# working.net
KiCad netlist of a schematic drawn in EAGLE
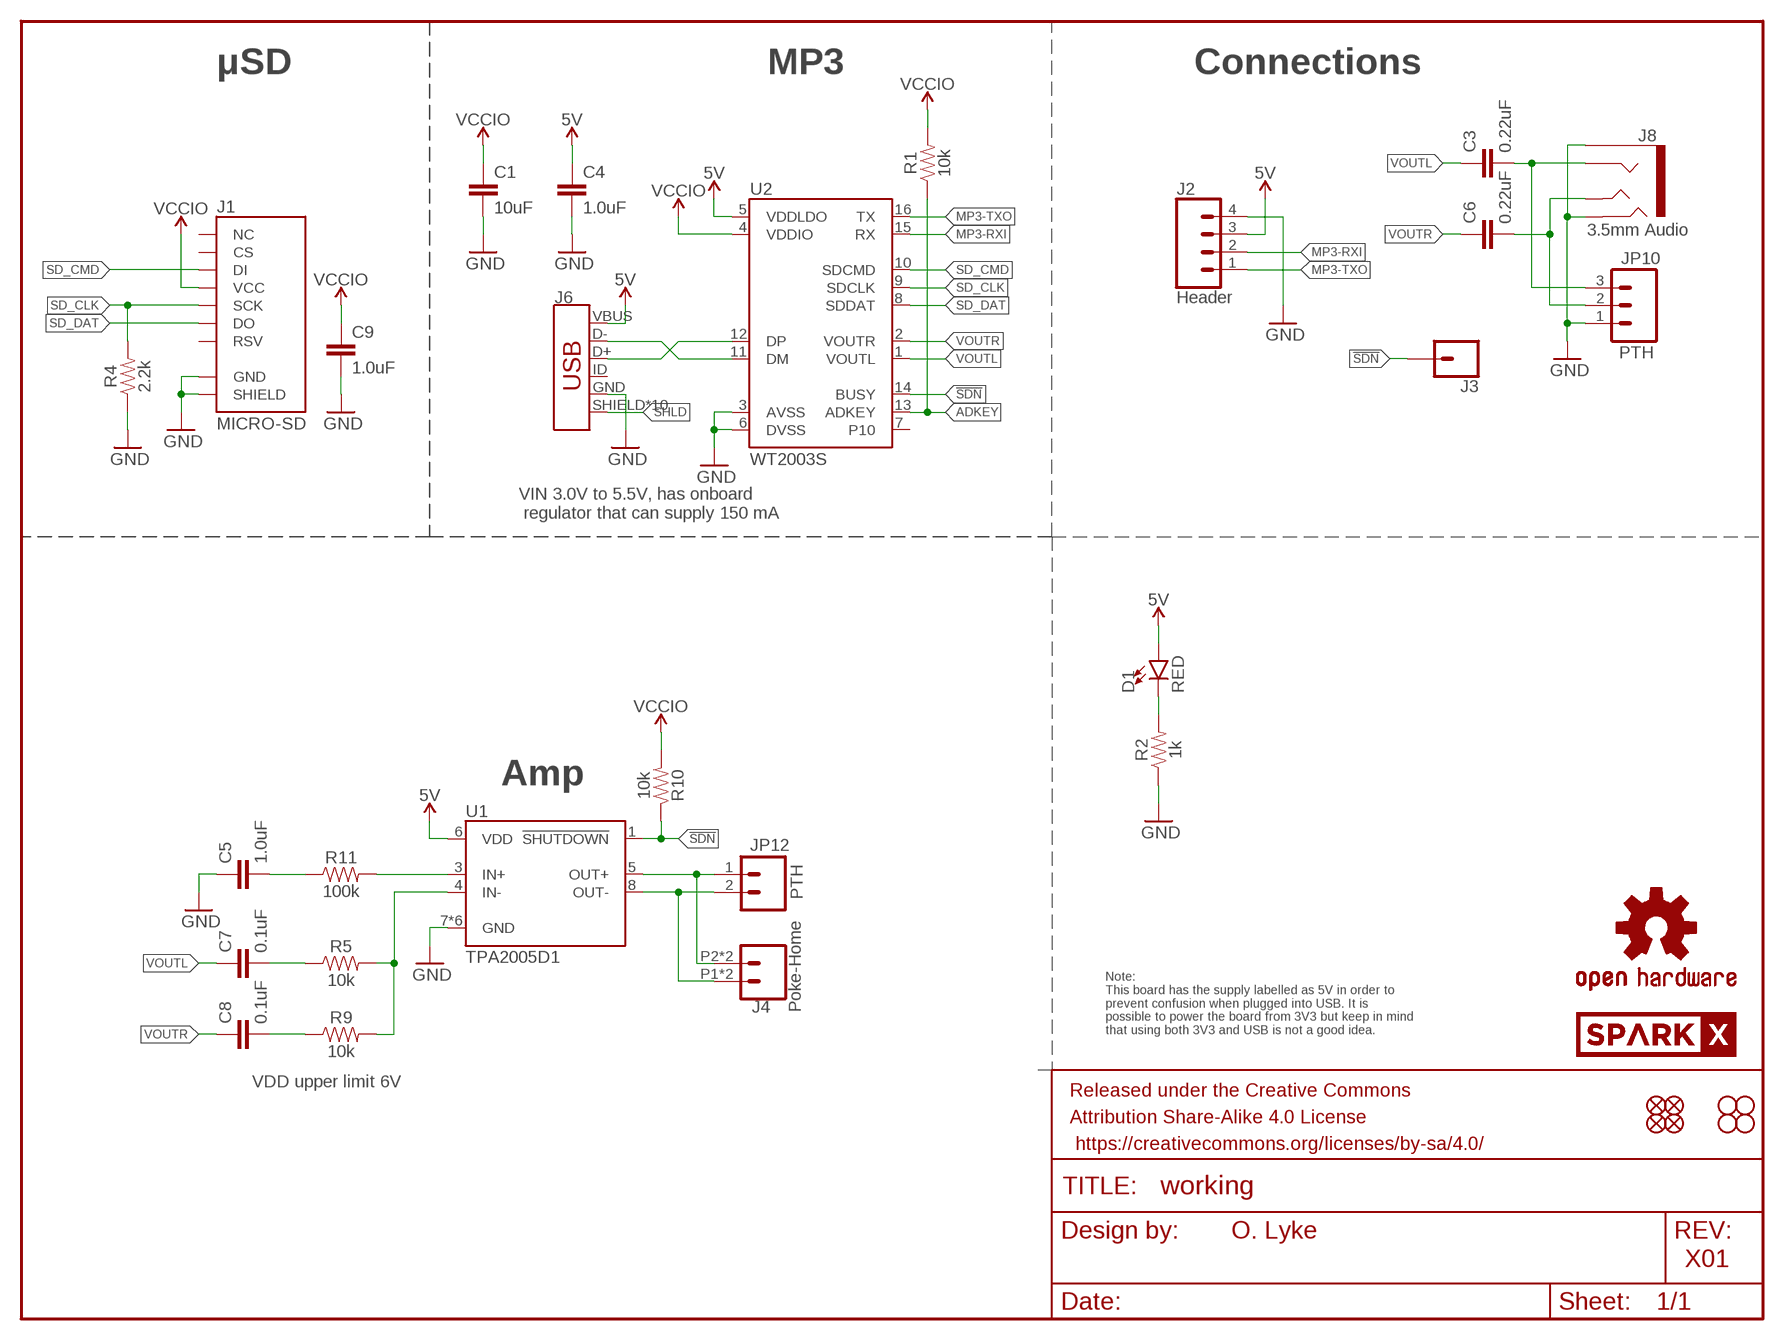
[diagram p0: schematic, sheet 1]

(export (version "E")
  (design (tool "Eeschema 10.0.6"))
  (components
    (comp (ref "C1")
      (value "10uF")
      (footprint "eagle-import:0603")
      (libsource (lib "eagle-import") (part "10UF-0603-6.3V-20%"))
    )
    (comp (ref "C3")
      (value "0.22uF")
      (footprint "eagle-import:0603")
      (libsource (lib "eagle-import") (part "0.22UF-0603-25V-10%"))
    )
    (comp (ref "C4")
      (value "1.0uF")
      (footprint "eagle-import:0603")
      (libsource (lib "eagle-import") (part "SparkFun-Capacitors_510_1.0UF-0603-16V-10%"))
    )
    (comp (ref "C5")
      (value "1.0uF")
      (footprint "eagle-import:0603")
      (libsource (lib "eagle-import") (part "SparkFun-Capacitors_510_1.0UF-0603-16V-10%"))
    )
    (comp (ref "C6")
      (value "0.22uF")
      (footprint "eagle-import:0603")
      (libsource (lib "eagle-import") (part "0.22UF-0603-25V-10%"))
    )
    (comp (ref "C7")
      (value "0.1uF")
      (footprint "eagle-import:0603")
      (libsource (lib "eagle-import") (part "0.1UF-0603-25V-(+80/-20%)"))
    )
    (comp (ref "C8")
      (value "0.1uF")
      (footprint "eagle-import:0603")
      (libsource (lib "eagle-import") (part "0.1UF-0603-25V-(+80/-20%)"))
    )
    (comp (ref "C9")
      (value "1.0uF")
      (footprint "eagle-import:0603")
      (libsource (lib "eagle-import") (part "1.0UF-0603-16V-10%"))
    )
    (comp (ref "D1")
      (value "RED")
      (footprint "eagle-import:LED-0603")
      (libsource (lib "eagle-import") (part "LED-RED0603"))
    )
    (comp (ref "FRAME1")
      (value "FRAME-LETTER")
      (footprint "eagle-import:CREATIVE_COMMONS")
      (libsource (lib "eagle-import") (part "FRAME-LETTER"))
    )
    (comp (ref "J1")
      (value "MICRO-SD")
      (footprint "eagle-import:MICRO-SD-SOCKET")
      (libsource (lib "eagle-import") (part "MICRO-SD_CARD_SOCKETPUSH-PUSH"))
    )
    (comp (ref "J2")
      (value "Header")
      (footprint "eagle-import:1X04_NO_SILK")
      (libsource (lib "eagle-import") (part "CONN_041X04_NO_SILK"))
    )
    (comp (ref "J3")
      (value "CONN_01PTH_NO_SILK_YES_STOP")
      (footprint "eagle-import:1X01_NO_SILK")
      (libsource (lib "eagle-import") (part "CONN_01PTH_NO_SILK_YES_STOP"))
    )
    (comp (ref "J4")
      (value "Poke-Home")
      (footprint "eagle-import:1X02_POKEHOME")
      (libsource (lib "eagle-import") (part "CONN_02SMALL_POKEHOME"))
    )
    (comp (ref "J6")
      (value "USB_MICRO-B_HALF_PTH_MILL")
      (footprint "eagle-import:USB-MICROB-PTH-MILL")
      (libsource (lib "eagle-import") (part "USB_MICRO-B_HALF_PTH_MILL"))
    )
    (comp (ref "J8")
      (value "3.5mm Audio")
      (footprint "eagle-import:AUDIO_JACK_3.5MM_TRRS_SMD_RA")
      (libsource (lib "eagle-import") (part "AUDIO_JACK_TRRSSMD_RA"))
    )
    (comp (ref "JP1")
      (value "FIDUCIALUFIDUCIAL")
      (footprint "eagle-import:MICRO-FIDUCIAL")
      (libsource (lib "eagle-import") (part "FIDUCIALUFIDUCIAL"))
    )
    (comp (ref "JP2")
      (value "FIDUCIALUFIDUCIAL")
      (footprint "eagle-import:MICRO-FIDUCIAL")
      (libsource (lib "eagle-import") (part "FIDUCIALUFIDUCIAL"))
    )
    (comp (ref "JP3")
      (value "STAND-OFF")
      (footprint "eagle-import:STAND-OFF")
      (libsource (lib "eagle-import") (part "STAND-OFF"))
    )
    (comp (ref "JP4")
      (value "STAND-OFF")
      (footprint "eagle-import:STAND-OFF")
      (libsource (lib "eagle-import") (part "STAND-OFF"))
    )
    (comp (ref "JP5")
      (value "FIDUCIALUFIDUCIAL")
      (footprint "eagle-import:MICRO-FIDUCIAL")
      (libsource (lib "eagle-import") (part "FIDUCIALUFIDUCIAL"))
    )
    (comp (ref "JP6")
      (value "FIDUCIALUFIDUCIAL")
      (footprint "eagle-import:MICRO-FIDUCIAL")
      (libsource (lib "eagle-import") (part "FIDUCIALUFIDUCIAL"))
    )
    (comp (ref "JP10")
      (value "PTH")
      (footprint "eagle-import:1X03_NO_SILK")
      (libsource (lib "eagle-import") (part "CONN_031X03_NO_SILK"))
    )
    (comp (ref "JP11")
      (value "STAND-OFF")
      (footprint "eagle-import:STAND-OFF")
      (libsource (lib "eagle-import") (part "STAND-OFF"))
    )
    (comp (ref "JP12")
      (value "PTH")
      (footprint "eagle-import:1X02_NO_SILK")
      (libsource (lib "eagle-import") (part "CONN_021X02_NO_SILK"))
    )
    (comp (ref "JP13")
      (value "STAND-OFF")
      (footprint "eagle-import:STAND-OFF")
      (libsource (lib "eagle-import") (part "STAND-OFF"))
    )
    (comp (ref "LOGO1")
      (value "OSHW-LOGOMINI")
      (footprint "eagle-import:OSHW-LOGO-MINI")
      (libsource (lib "eagle-import") (part "OSHW-LOGOMINI"))
    )
    (comp (ref "R1")
      (value "10k")
      (footprint "eagle-import:0603")
      (libsource (lib "eagle-import") (part "10KOHM-0603-1/10W-1%"))
    )
    (comp (ref "R2")
      (value "1k")
      (footprint "eagle-import:0603")
      (libsource (lib "eagle-import") (part "1KOHM-0603-1/10W-1%"))
    )
    (comp (ref "R4")
      (value "2.2k")
      (footprint "eagle-import:0603")
      (libsource (lib "eagle-import") (part "2.2KOHM-0603-1/10W-1%"))
    )
    (comp (ref "R5")
      (value "10k")
      (footprint "eagle-import:0603")
      (libsource (lib "eagle-import") (part "10KOHM-0603-1/10W-1%"))
    )
    (comp (ref "R9")
      (value "10k")
      (footprint "eagle-import:0603")
      (libsource (lib "eagle-import") (part "10KOHM-0603-1/10W-1%"))
    )
    (comp (ref "R10")
      (value "10k")
      (footprint "eagle-import:0603")
      (libsource (lib "eagle-import") (part "10KOHM-0603-1/10W-1%"))
    )
    (comp (ref "R11")
      (value "100k")
      (footprint "eagle-import:0603")
      (libsource (lib "eagle-import") (part "100KOHM-0603-1/10W-1%"))
    )
    (comp (ref "U$2")
      (value "SPARKX-LOGO4")
      (footprint "eagle-import:SPARKX-MEDIUM")
      (libsource (lib "eagle-import") (part "SPARKX-LOGO4"))
    )
    (comp (ref "U1")
      (value "TPA2005D1")
      (footprint "eagle-import:QFN-8_PAD")
      (libsource (lib "eagle-import") (part "TPA2005D1DRB"))
    )
    (comp (ref "U2")
      (value "WT2003S")
      (footprint "eagle-import:SO16")
      (libsource (lib "eagle-import") (part "WT2003S"))
    )
  )
  (nets
    (net (code "1") (name "/~{SDN}") (class "Default")
      (node (ref "J3") (pin "1") (pinfunction "1_1") (pintype "passive"))
      (node (ref "R10") (pin "1") (pinfunction "1_1") (pintype "passive"))
      (node (ref "U1") (pin "1") (pinfunction "~{SHUTDOWN}_1") (pintype "input"))
      (node (ref "U2") (pin "14") (pinfunction "BUSY_14") (pintype "bidirectional"))
    )
    (net (code "2") (name "5V") (class "Default")
      (node (ref "C4") (pin "1") (pinfunction "1_1") (pintype "passive"))
      (node (ref "D1") (pin "A") (pinfunction "A_A") (pintype "passive"))
      (node (ref "J2") (pin "3") (pinfunction "3_3") (pintype "passive"))
      (node (ref "J6") (pin "VBUS") (pinfunction "VBUS_VBUS") (pintype "power_in"))
      (node (ref "U1") (pin "6") (pinfunction "VDD_6") (pintype "power_in"))
      (node (ref "U2") (pin "5") (pinfunction "VDDLDO_5") (pintype "bidirectional"))
    )
    (net (code "3") (name "ADKEY") (class "Default")
      (node (ref "R1") (pin "1") (pinfunction "1_1") (pintype "passive"))
      (node (ref "U2") (pin "13") (pinfunction "ADKEY_13") (pintype "bidirectional"))
    )
    (net (code "4") (name "GND") (class "Default")
      (node (ref "C1") (pin "2") (pinfunction "2_2") (pintype "passive"))
      (node (ref "C4") (pin "2") (pinfunction "2_2") (pintype "passive"))
      (node (ref "C5") (pin "1") (pinfunction "1_1") (pintype "passive"))
      (node (ref "C9") (pin "2") (pinfunction "2_2") (pintype "passive"))
      (node (ref "J1") (pin "CD1") (pinfunction "SHIELD_CD1") (pintype "bidirectional"))
      (node (ref "J1") (pin "GND") (pinfunction "GND_GND") (pintype "bidirectional"))
      (node (ref "J2") (pin "4") (pinfunction "4_4") (pintype "passive"))
      (node (ref "J6") (pin "GND") (pinfunction "GND_GND") (pintype "power_in"))
      (node (ref "J8") (pin "EARTH") (pinfunction "EARTH_EARTH") (pintype "bidirectional"))
      (node (ref "J8") (pin "RING2") (pinfunction "RING2_RING2") (pintype "bidirectional"))
      (node (ref "JP10") (pin "1") (pinfunction "1_1") (pintype "passive"))
      (node (ref "R2") (pin "1") (pinfunction "1_1") (pintype "passive"))
      (node (ref "R4") (pin "1") (pinfunction "1_1") (pintype "passive"))
      (node (ref "U1") (pin "10") (pinfunction "GND_10") (pintype "power_in"))
      (node (ref "U1") (pin "11") (pinfunction "GND_11") (pintype "power_in"))
      (node (ref "U1") (pin "12") (pinfunction "GND_12") (pintype "power_in"))
      (node (ref "U1") (pin "13") (pinfunction "GND_13") (pintype "power_in"))
      (node (ref "U1") (pin "7") (pinfunction "GND_7") (pintype "power_in"))
      (node (ref "U1") (pin "9") (pinfunction "GND_9") (pintype "power_in"))
      (node (ref "U2") (pin "3") (pinfunction "AVSS_3") (pintype "bidirectional"))
      (node (ref "U2") (pin "6") (pinfunction "DVSS_6") (pintype "bidirectional"))
    )
    (net (code "5") (name "MP3-RXI") (class "Default")
      (node (ref "J2") (pin "2") (pinfunction "2_2") (pintype "passive"))
      (node (ref "U2") (pin "15") (pinfunction "RX_15") (pintype "bidirectional"))
    )
    (net (code "6") (name "MP3-TXO") (class "Default")
      (node (ref "J2") (pin "1") (pinfunction "1_1") (pintype "passive"))
      (node (ref "U2") (pin "16") (pinfunction "TX_16") (pintype "bidirectional"))
    )
    (net (code "7") (name "Net-(C3-Pad2)") (class "Default")
      (node (ref "C3") (pin "2") (pinfunction "2_2") (pintype "passive"))
      (node (ref "J8") (pin "RING1") (pinfunction "RING1_RING1") (pintype "bidirectional"))
      (node (ref "JP10") (pin "3") (pinfunction "3_3") (pintype "passive"))
    )
    (net (code "8") (name "Net-(C5-Pad2)") (class "Default")
      (node (ref "C5") (pin "2") (pinfunction "2_2") (pintype "passive"))
      (node (ref "R11") (pin "1") (pinfunction "1_1") (pintype "passive"))
    )
    (net (code "9") (name "Net-(C6-Pad2)") (class "Default")
      (node (ref "C6") (pin "2") (pinfunction "2_2") (pintype "passive"))
      (node (ref "J8") (pin "TIP") (pinfunction "TIP_TIP") (pintype "bidirectional"))
      (node (ref "JP10") (pin "2") (pinfunction "2_2") (pintype "passive"))
    )
    (net (code "10") (name "Net-(C7-Pad2)") (class "Default")
      (node (ref "C7") (pin "2") (pinfunction "2_2") (pintype "passive"))
      (node (ref "R5") (pin "1") (pinfunction "1_1") (pintype "passive"))
    )
    (net (code "11") (name "Net-(C8-Pad2)") (class "Default")
      (node (ref "C8") (pin "2") (pinfunction "2_2") (pintype "passive"))
      (node (ref "R9") (pin "1") (pinfunction "1_1") (pintype "passive"))
    )
    (net (code "12") (name "Net-(D1-PadC)") (class "Default")
      (node (ref "D1") (pin "C") (pinfunction "C_C") (pintype "passive"))
      (node (ref "R2") (pin "2") (pinfunction "2_2") (pintype "passive"))
    )
    (net (code "13") (name "Net-(U1-IN+)") (class "Default")
      (node (ref "R11") (pin "2") (pinfunction "2_2") (pintype "passive"))
      (node (ref "U1") (pin "3") (pinfunction "IN+_3") (pintype "bidirectional"))
    )
    (net (code "14") (name "Net-(U1-IN-)") (class "Default")
      (node (ref "R5") (pin "2") (pinfunction "2_2") (pintype "passive"))
      (node (ref "R9") (pin "2") (pinfunction "2_2") (pintype "passive"))
      (node (ref "U1") (pin "4") (pinfunction "IN-_4") (pintype "bidirectional"))
    )
    (net (code "15") (name "Net-(U1-OUT+)") (class "Default")
      (node (ref "J4") (pin "P2") (pinfunction "2_P2") (pintype "passive"))
      (node (ref "J4") (pin "P4") (pinfunction "2_P4") (pintype "passive"))
      (node (ref "JP12") (pin "1") (pinfunction "1_1") (pintype "passive"))
      (node (ref "U1") (pin "5") (pinfunction "OUT+_5") (pintype "bidirectional"))
    )
    (net (code "16") (name "Net-(U1-OUT-)") (class "Default")
      (node (ref "J4") (pin "P1") (pinfunction "1_P1") (pintype "passive"))
      (node (ref "J4") (pin "P3") (pinfunction "1_P3") (pintype "passive"))
      (node (ref "JP12") (pin "2") (pinfunction "2_2") (pintype "passive"))
      (node (ref "U1") (pin "8") (pinfunction "OUT-_8") (pintype "bidirectional"))
    )
    (net (code "17") (name "Net-(U2-DM)") (class "Default")
      (node (ref "J6") (pin "D-") (pinfunction "D-_D-") (pintype "bidirectional"))
      (node (ref "U2") (pin "11") (pinfunction "DM_11") (pintype "bidirectional"))
    )
    (net (code "18") (name "Net-(U2-DP)") (class "Default")
      (node (ref "J6") (pin "D+") (pinfunction "D+_D+") (pintype "bidirectional"))
      (node (ref "U2") (pin "12") (pinfunction "DP_12") (pintype "bidirectional"))
    )
    (net (code "19") (name "SD_CLK") (class "Default")
      (node (ref "J1") (pin "SCLK") (pinfunction "SCK_SCLK") (pintype "bidirectional"))
      (node (ref "R4") (pin "2") (pinfunction "2_2") (pintype "passive"))
      (node (ref "U2") (pin "9") (pinfunction "SDCLK_9") (pintype "bidirectional"))
    )
    (net (code "20") (name "SD_CMD") (class "Default")
      (node (ref "J1") (pin "DI") (pinfunction "DI_DI") (pintype "bidirectional"))
      (node (ref "U2") (pin "10") (pinfunction "SDCMD_10") (pintype "bidirectional"))
    )
    (net (code "21") (name "SD_DAT") (class "Default")
      (node (ref "J1") (pin "DO") (pinfunction "DO_DO") (pintype "bidirectional"))
      (node (ref "U2") (pin "8") (pinfunction "SDDAT_8") (pintype "bidirectional"))
    )
    (net (code "22") (name "SHLD") (class "Default")
      (node (ref "J6") (pin "SHIELD") (pinfunction "SHIELD_SHIELD") (pintype "bidirectional"))
      (node (ref "J6") (pin "SHIELD10") (pinfunction "SHIELD_SHIELD10") (pintype "bidirectional"))
      (node (ref "J6") (pin "SHIELD2") (pinfunction "SHIELD_SHIELD2") (pintype "bidirectional"))
      (node (ref "J6") (pin "SHIELD3") (pinfunction "SHIELD_SHIELD3") (pintype "bidirectional"))
      (node (ref "J6") (pin "SHIELD4") (pinfunction "SHIELD_SHIELD4") (pintype "bidirectional"))
      (node (ref "J6") (pin "SHIELD5") (pinfunction "SHIELD_SHIELD5") (pintype "bidirectional"))
      (node (ref "J6") (pin "SHIELD6") (pinfunction "SHIELD_SHIELD6") (pintype "bidirectional"))
      (node (ref "J6") (pin "SHIELD7") (pinfunction "SHIELD_SHIELD7") (pintype "bidirectional"))
      (node (ref "J6") (pin "SHIELD8") (pinfunction "SHIELD_SHIELD8") (pintype "bidirectional"))
      (node (ref "J6") (pin "SHIELD9") (pinfunction "SHIELD_SHIELD9") (pintype "bidirectional"))
    )
    (net (code "23") (name "VCCIO") (class "Default")
      (node (ref "C1") (pin "1") (pinfunction "1_1") (pintype "passive"))
      (node (ref "C9") (pin "1") (pinfunction "1_1") (pintype "passive"))
      (node (ref "J1") (pin "VCC") (pinfunction "VCC_VCC") (pintype "bidirectional"))
      (node (ref "R1") (pin "2") (pinfunction "2_2") (pintype "passive"))
      (node (ref "R10") (pin "2") (pinfunction "2_2") (pintype "passive"))
      (node (ref "U2") (pin "4") (pinfunction "VDDIO_4") (pintype "bidirectional"))
    )
    (net (code "24") (name "VOUTL") (class "Default")
      (node (ref "C3") (pin "1") (pinfunction "1_1") (pintype "passive"))
      (node (ref "C7") (pin "1") (pinfunction "1_1") (pintype "passive"))
      (node (ref "U2") (pin "1") (pinfunction "VOUTL_1") (pintype "bidirectional"))
    )
    (net (code "25") (name "VOUTR") (class "Default")
      (node (ref "C6") (pin "1") (pinfunction "1_1") (pintype "passive"))
      (node (ref "C8") (pin "1") (pinfunction "1_1") (pintype "passive"))
      (node (ref "U2") (pin "2") (pinfunction "VOUTR_2") (pintype "bidirectional"))
    )
    (net (code "26") (name "unconnected-(J1-NC-PadRSV2)") (class "Default")
      (node (ref "J1") (pin "RSV2") (pinfunction "NC_RSV2") (pintype "bidirectional"))
    )
    (net (code "27") (name "unconnected-(J1-PadCS)") (class "Default")
      (node (ref "J1") (pin "CS") (pinfunction "CS_CS") (pintype "bidirectional"))
    )
    (net (code "28") (name "unconnected-(J1-RSV-PadRSV1)") (class "Default")
      (node (ref "J1") (pin "RSV1") (pinfunction "RSV_RSV1") (pintype "bidirectional"))
    )
    (net (code "29") (name "unconnected-(J6-PadID)") (class "Default")
      (node (ref "J6") (pin "ID") (pinfunction "ID_ID") (pintype "bidirectional"))
    )
    (net (code "30") (name "unconnected-(U2-P10-Pad7)") (class "Default")
      (node (ref "U2") (pin "7") (pinfunction "P10_7") (pintype "bidirectional"))
    )
  )
)
